# FuelGauge.net
KiCad netlist of a schematic drawn in Altium Designer
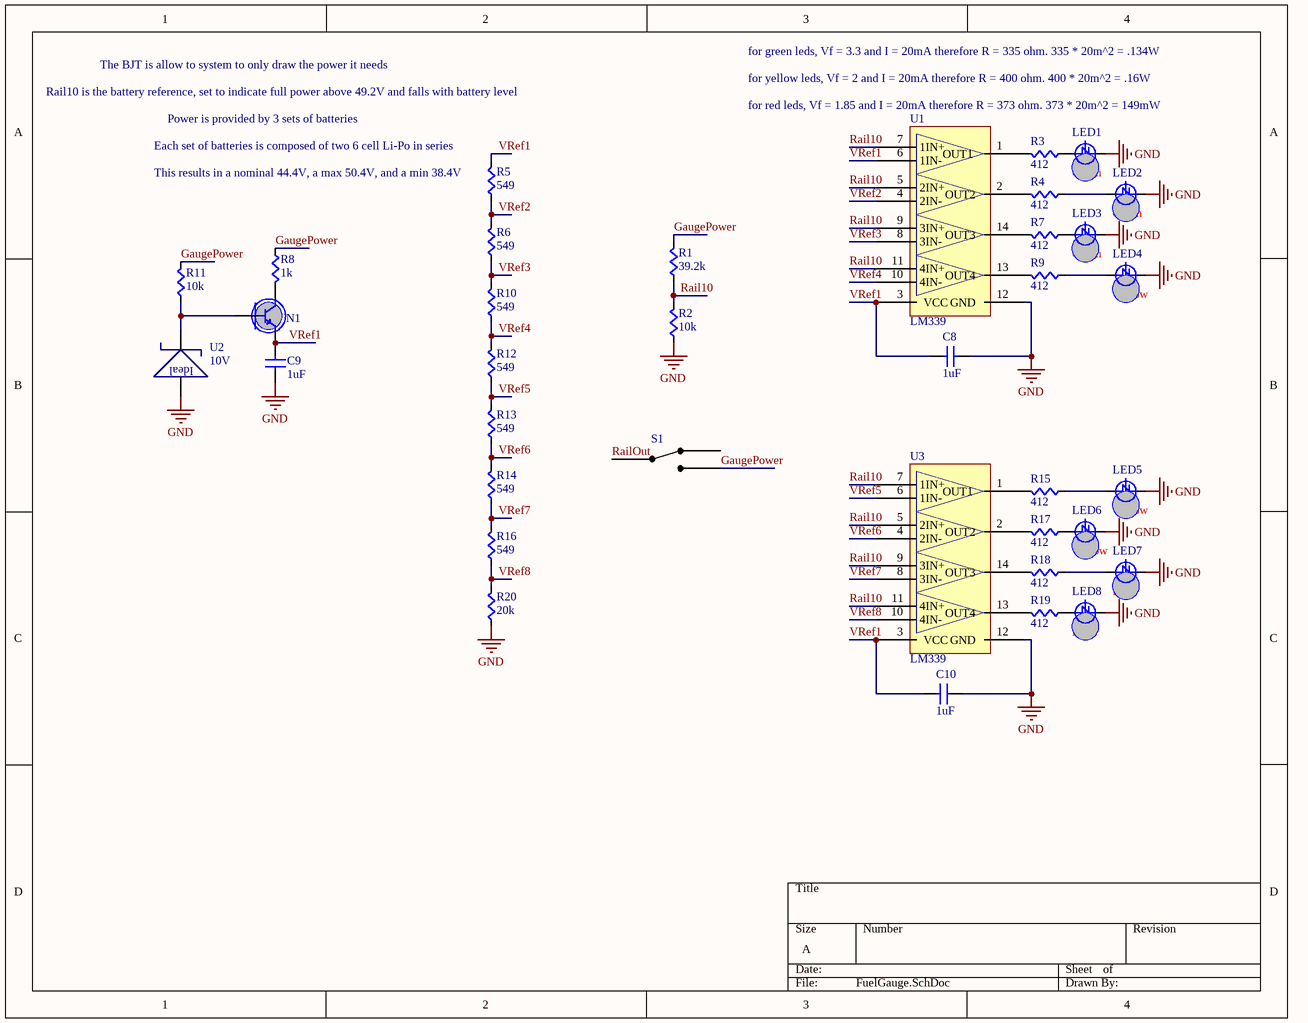
[diagram p0: FuelGauge.SchDoc]

(export (version "E")
  (design (tool "Eeschema 10.0.6"))
  (components
    (comp (ref "C8")
      (value "1uF")
      (footprint "CAPC0603")
      (fields (field (name "Comment") "Cap"))
      (libsource (lib "SubjuGator8") (part "Cap"))
    )
    (comp (ref "C9")
      (value "1uF")
      (footprint "CAPC0603")
      (fields (field (name "Comment") "Cap"))
      (libsource (lib "SubjuGator8") (part "Cap"))
    )
    (comp (ref "C10")
      (value "1uF")
      (footprint "CAPC0603")
      (fields (field (name "Comment") "Cap"))
      (libsource (lib "SubjuGator8") (part "Cap"))
    )
    (comp (ref "LED1")
      (value "LED")
      (footprint "LED0603")
      (fields (field (name "COLOR") "Green"))
      (libsource (lib "SubjuGator8") (part "LED"))
    )
    (comp (ref "LED2")
      (value "LED")
      (footprint "LED0603")
      (fields (field (name "COLOR") "Green"))
      (libsource (lib "SubjuGator8") (part "LED"))
    )
    (comp (ref "LED3")
      (value "LED")
      (footprint "LED0603")
      (fields (field (name "COLOR") "Green"))
      (libsource (lib "SubjuGator8") (part "LED"))
    )
    (comp (ref "LED4")
      (value "LED")
      (footprint "LED0603")
      (fields (field (name "COLOR") "Yellow"))
      (libsource (lib "SubjuGator8") (part "LED"))
    )
    (comp (ref "LED5")
      (value "LED")
      (footprint "LED0603")
      (fields (field (name "COLOR") "Yellow"))
      (libsource (lib "SubjuGator8") (part "LED"))
    )
    (comp (ref "LED6")
      (value "LED")
      (footprint "LED0603")
      (fields (field (name "COLOR") "Yellow"))
      (libsource (lib "SubjuGator8") (part "LED"))
    )
    (comp (ref "LED7")
      (value "LED")
      (footprint "LED0603")
      (fields (field (name "COLOR") "Red"))
      (libsource (lib "SubjuGator8") (part "LED"))
    )
    (comp (ref "LED8")
      (value "LED")
      (footprint "LED0603")
      (fields (field (name "COLOR") "Red"))
      (libsource (lib "SubjuGator8") (part "LED"))
    )
    (comp (ref "N1")
      (value "NPNBJT")
      (footprint "PZT3904")
      (description "NPN Transistor Template")
      (libsource (lib "SubjuGator8") (part "NPNBJT"))
    )
    (comp (ref "R1")
      (value "39.2k")
      (footprint "RES0603")
      (fields (field (name "Comment") "Res"))
      (libsource (lib "SubjuGator8") (part "Res"))
    )
    (comp (ref "R2")
      (value "10k")
      (footprint "RES0603")
      (fields (field (name "Comment") "Res"))
      (libsource (lib "SubjuGator8") (part "Res"))
    )
    (comp (ref "R3")
      (value "412")
      (footprint "RES1206")
      (fields (field (name "Comment") "Res"))
      (libsource (lib "SubjuGator8") (part "Res"))
    )
    (comp (ref "R4")
      (value "412")
      (footprint "RES1206")
      (fields (field (name "Comment") "Res"))
      (libsource (lib "SubjuGator8") (part "Res"))
    )
    (comp (ref "R5")
      (value "549")
      (footprint "RES0603")
      (fields (field (name "Comment") "Res"))
      (libsource (lib "SubjuGator8") (part "Res"))
    )
    (comp (ref "R6")
      (value "549")
      (footprint "RES0603")
      (fields (field (name "Comment") "Res"))
      (libsource (lib "SubjuGator8") (part "Res"))
    )
    (comp (ref "R7")
      (value "412")
      (footprint "RES1206")
      (fields (field (name "Comment") "Res"))
      (libsource (lib "SubjuGator8") (part "Res"))
    )
    (comp (ref "R8")
      (value "1k")
      (footprint "RES1206")
      (fields (field (name "Comment") "Res"))
      (libsource (lib "SubjuGator8") (part "Res"))
    )
    (comp (ref "R9")
      (value "412")
      (footprint "RES1206")
      (fields (field (name "Comment") "Res"))
      (libsource (lib "SubjuGator8") (part "Res"))
    )
    (comp (ref "R10")
      (value "549")
      (footprint "RES0603")
      (fields (field (name "Comment") "Res"))
      (libsource (lib "SubjuGator8") (part "Res"))
    )
    (comp (ref "R11")
      (value "10k")
      (footprint "RES0603")
      (fields (field (name "Comment") "Res"))
      (libsource (lib "SubjuGator8") (part "Res"))
    )
    (comp (ref "R12")
      (value "549")
      (footprint "RES0603")
      (fields (field (name "Comment") "Res"))
      (libsource (lib "SubjuGator8") (part "Res"))
    )
    (comp (ref "R13")
      (value "549")
      (footprint "RES0603")
      (fields (field (name "Comment") "Res"))
      (libsource (lib "SubjuGator8") (part "Res"))
    )
    (comp (ref "R14")
      (value "549")
      (footprint "RES0603")
      (fields (field (name "Comment") "Res"))
      (libsource (lib "SubjuGator8") (part "Res"))
    )
    (comp (ref "R15")
      (value "412")
      (footprint "RES1206")
      (fields (field (name "Comment") "Res"))
      (libsource (lib "SubjuGator8") (part "Res"))
    )
    (comp (ref "R16")
      (value "549")
      (footprint "RES0603")
      (fields (field (name "Comment") "Res"))
      (libsource (lib "SubjuGator8") (part "Res"))
    )
    (comp (ref "R17")
      (value "412")
      (footprint "RES1206")
      (fields (field (name "Comment") "Res"))
      (libsource (lib "SubjuGator8") (part "Res"))
    )
    (comp (ref "R18")
      (value "412")
      (footprint "RES1206")
      (fields (field (name "Comment") "Res"))
      (libsource (lib "SubjuGator8") (part "Res"))
    )
    (comp (ref "R19")
      (value "412")
      (footprint "RES1206")
      (fields (field (name "Comment") "Res"))
      (libsource (lib "SubjuGator8") (part "Res"))
    )
    (comp (ref "R20")
      (value "20k")
      (footprint "RES0603")
      (fields (field (name "Comment") "Res"))
      (libsource (lib "SubjuGator8") (part "Res"))
    )
    (comp (ref "S1")
      (value "SPDT Slide Switch")
      (footprint "CL-SB-12B-01T")
      (libsource (lib "SubjuGator8") (part "SPDT Slide Switch"))
    )
    (comp (ref "U1")
      (value "LM339")
      (footprint "LM339")
      (description "IC QUAD DIFF COMPARATOR 14-TSSOP")
      (libsource (lib "SubjuGator8") (part "LM339"))
    )
    (comp (ref "U2")
      (value "LM4040")
      (footprint "LM4040")
      (description "LM4040AIM3-10.0/NOPBCT")
      (fields (field (name "REVERSE BREAKDOWN VOLTAGE") "10V"))
      (libsource (lib "SubjuGator8") (part "LM4040"))
    )
    (comp (ref "U3")
      (value "LM339")
      (footprint "LM339")
      (description "IC QUAD DIFF COMPARATOR 14-TSSOP")
      (libsource (lib "SubjuGator8") (part "LM339"))
    )
  )
  (nets
    (net (code "1") (name "/GaugePower") (class "Default")
      (node (ref "R1") (pin "1") (pinfunction "A_1") (pintype "passive"))
      (node (ref "R11") (pin "1") (pinfunction "A_1") (pintype "passive"))
      (node (ref "R8") (pin "2") (pinfunction "B_2") (pintype "passive"))
      (node (ref "S1") (pin "3") (pinfunction "3_3") (pintype "passive"))
    )
    (net (code "2") (name "/Rail10") (class "Default")
      (node (ref "R1") (pin "2") (pinfunction "B_2") (pintype "passive"))
      (node (ref "R2") (pin "1") (pinfunction "A_1") (pintype "passive"))
      (node (ref "U1") (pin "11") (pinfunction "4IN+_11") (pintype "passive"))
      (node (ref "U1") (pin "5") (pinfunction "2IN+_5") (pintype "passive"))
      (node (ref "U1") (pin "7") (pinfunction "1IN+_7") (pintype "passive"))
      (node (ref "U1") (pin "9") (pinfunction "3IN+_9") (pintype "passive"))
      (node (ref "U3") (pin "11") (pinfunction "4IN+_11") (pintype "passive"))
      (node (ref "U3") (pin "5") (pinfunction "2IN+_5") (pintype "passive"))
      (node (ref "U3") (pin "7") (pinfunction "1IN+_7") (pintype "passive"))
      (node (ref "U3") (pin "9") (pinfunction "3IN+_9") (pintype "passive"))
    )
    (net (code "3") (name "/RailOut") (class "Default")
      (node (ref "S1") (pin "2") (pinfunction "2_2") (pintype "passive"))
    )
    (net (code "4") (name "/VRef1") (class "Default")
      (node (ref "C10") (pin "1") (pinfunction "A_1") (pintype "passive"))
      (node (ref "C8") (pin "1") (pinfunction "A_1") (pintype "passive"))
      (node (ref "C9") (pin "1") (pinfunction "A_1") (pintype "passive"))
      (node (ref "N1") (pin "E") (pinfunction "E_E") (pintype "passive"))
      (node (ref "R5") (pin "1") (pinfunction "A_1") (pintype "passive"))
      (node (ref "U1") (pin "3") (pinfunction "VCC_3") (pintype "passive"))
      (node (ref "U1") (pin "6") (pinfunction "1IN-_6") (pintype "passive"))
      (node (ref "U3") (pin "3") (pinfunction "VCC_3") (pintype "passive"))
    )
    (net (code "5") (name "/VRef2") (class "Default")
      (node (ref "R5") (pin "2") (pinfunction "B_2") (pintype "passive"))
      (node (ref "R6") (pin "1") (pinfunction "A_1") (pintype "passive"))
      (node (ref "U1") (pin "4") (pinfunction "2IN-_4") (pintype "passive"))
    )
    (net (code "6") (name "/VRef3") (class "Default")
      (node (ref "R10") (pin "1") (pinfunction "A_1") (pintype "passive"))
      (node (ref "R6") (pin "2") (pinfunction "B_2") (pintype "passive"))
      (node (ref "U1") (pin "8") (pinfunction "3IN-_8") (pintype "passive"))
    )
    (net (code "7") (name "/VRef4") (class "Default")
      (node (ref "R10") (pin "2") (pinfunction "B_2") (pintype "passive"))
      (node (ref "R12") (pin "1") (pinfunction "A_1") (pintype "passive"))
      (node (ref "U1") (pin "10") (pinfunction "4IN-_10") (pintype "passive"))
    )
    (net (code "8") (name "/VRef5") (class "Default")
      (node (ref "R12") (pin "2") (pinfunction "B_2") (pintype "passive"))
      (node (ref "R13") (pin "1") (pinfunction "A_1") (pintype "passive"))
      (node (ref "U3") (pin "6") (pinfunction "1IN-_6") (pintype "passive"))
    )
    (net (code "9") (name "/VRef6") (class "Default")
      (node (ref "R13") (pin "2") (pinfunction "B_2") (pintype "passive"))
      (node (ref "R14") (pin "1") (pinfunction "A_1") (pintype "passive"))
      (node (ref "U3") (pin "4") (pinfunction "2IN-_4") (pintype "passive"))
    )
    (net (code "10") (name "/VRef7") (class "Default")
      (node (ref "R14") (pin "2") (pinfunction "B_2") (pintype "passive"))
      (node (ref "R16") (pin "1") (pinfunction "A_1") (pintype "passive"))
      (node (ref "U3") (pin "8") (pinfunction "3IN-_8") (pintype "passive"))
    )
    (net (code "11") (name "/VRef8") (class "Default")
      (node (ref "R16") (pin "2") (pinfunction "B_2") (pintype "passive"))
      (node (ref "R20") (pin "1") (pinfunction "A_1") (pintype "passive"))
      (node (ref "U3") (pin "10") (pinfunction "4IN-_10") (pintype "passive"))
    )
    (net (code "12") (name "GND") (class "Default")
      (node (ref "C10") (pin "2") (pinfunction "B_2") (pintype "passive"))
      (node (ref "C8") (pin "2") (pinfunction "B_2") (pintype "passive"))
      (node (ref "C9") (pin "2") (pinfunction "B_2") (pintype "passive"))
      (node (ref "LED1") (pin "C") (pinfunction "C_C") (pintype "passive"))
      (node (ref "LED2") (pin "C") (pinfunction "C_C") (pintype "passive"))
      (node (ref "LED3") (pin "C") (pinfunction "C_C") (pintype "passive"))
      (node (ref "LED4") (pin "C") (pinfunction "C_C") (pintype "passive"))
      (node (ref "LED5") (pin "C") (pinfunction "C_C") (pintype "passive"))
      (node (ref "LED6") (pin "C") (pinfunction "C_C") (pintype "passive"))
      (node (ref "LED7") (pin "C") (pinfunction "C_C") (pintype "passive"))
      (node (ref "LED8") (pin "C") (pinfunction "C_C") (pintype "passive"))
      (node (ref "R2") (pin "2") (pinfunction "B_2") (pintype "passive"))
      (node (ref "R20") (pin "2") (pinfunction "B_2") (pintype "passive"))
      (node (ref "U1") (pin "12") (pinfunction "GND_12") (pintype "passive"))
      (node (ref "U2") (pin "2") (pinfunction "Cathode_2") (pintype "passive"))
      (node (ref "U3") (pin "12") (pinfunction "GND_12") (pintype "passive"))
    )
    (net (code "13") (name "Net-(R3-A)") (class "Default")
      (node (ref "R3") (pin "1") (pinfunction "A_1") (pintype "passive"))
      (node (ref "U1") (pin "1") (pinfunction "OUT1_1") (pintype "passive"))
    )
    (net (code "14") (name "Net-(R3-B)") (class "Default")
      (node (ref "LED1") (pin "A") (pinfunction "A_A") (pintype "passive"))
      (node (ref "R3") (pin "2") (pinfunction "B_2") (pintype "passive"))
    )
    (net (code "15") (name "Net-(R4-A)") (class "Default")
      (node (ref "R4") (pin "1") (pinfunction "A_1") (pintype "passive"))
      (node (ref "U1") (pin "2") (pinfunction "OUT2_2") (pintype "passive"))
    )
    (net (code "16") (name "Net-(R4-B)") (class "Default")
      (node (ref "LED2") (pin "A") (pinfunction "A_A") (pintype "passive"))
      (node (ref "R4") (pin "2") (pinfunction "B_2") (pintype "passive"))
    )
    (net (code "17") (name "Net-(R7-A)") (class "Default")
      (node (ref "R7") (pin "1") (pinfunction "A_1") (pintype "passive"))
      (node (ref "U1") (pin "14") (pinfunction "OUT3_14") (pintype "passive"))
    )
    (net (code "18") (name "Net-(R7-B)") (class "Default")
      (node (ref "LED3") (pin "A") (pinfunction "A_A") (pintype "passive"))
      (node (ref "R7") (pin "2") (pinfunction "B_2") (pintype "passive"))
    )
    (net (code "19") (name "Net-(R8-A)") (class "Default")
      (node (ref "N1") (pin "C") (pinfunction "C_C") (pintype "passive"))
      (node (ref "R8") (pin "1") (pinfunction "A_1") (pintype "passive"))
    )
    (net (code "20") (name "Net-(R9-A)") (class "Default")
      (node (ref "R9") (pin "1") (pinfunction "A_1") (pintype "passive"))
      (node (ref "U1") (pin "13") (pinfunction "OUT4_13") (pintype "passive"))
    )
    (net (code "21") (name "Net-(R9-B)") (class "Default")
      (node (ref "LED4") (pin "A") (pinfunction "A_A") (pintype "passive"))
      (node (ref "R9") (pin "2") (pinfunction "B_2") (pintype "passive"))
    )
    (net (code "22") (name "Net-(R11-B)") (class "Default")
      (node (ref "N1") (pin "B") (pinfunction "B_B") (pintype "passive"))
      (node (ref "R11") (pin "2") (pinfunction "B_2") (pintype "passive"))
      (node (ref "U2") (pin "1") (pinfunction "Anode_1") (pintype "passive"))
    )
    (net (code "23") (name "Net-(R15-A)") (class "Default")
      (node (ref "R15") (pin "1") (pinfunction "A_1") (pintype "passive"))
      (node (ref "U3") (pin "1") (pinfunction "OUT1_1") (pintype "passive"))
    )
    (net (code "24") (name "Net-(R15-B)") (class "Default")
      (node (ref "LED5") (pin "A") (pinfunction "A_A") (pintype "passive"))
      (node (ref "R15") (pin "2") (pinfunction "B_2") (pintype "passive"))
    )
    (net (code "25") (name "Net-(R17-A)") (class "Default")
      (node (ref "R17") (pin "1") (pinfunction "A_1") (pintype "passive"))
      (node (ref "U3") (pin "2") (pinfunction "OUT2_2") (pintype "passive"))
    )
    (net (code "26") (name "Net-(R17-B)") (class "Default")
      (node (ref "LED6") (pin "A") (pinfunction "A_A") (pintype "passive"))
      (node (ref "R17") (pin "2") (pinfunction "B_2") (pintype "passive"))
    )
    (net (code "27") (name "Net-(R18-A)") (class "Default")
      (node (ref "R18") (pin "1") (pinfunction "A_1") (pintype "passive"))
      (node (ref "U3") (pin "14") (pinfunction "OUT3_14") (pintype "passive"))
    )
    (net (code "28") (name "Net-(R18-B)") (class "Default")
      (node (ref "LED7") (pin "A") (pinfunction "A_A") (pintype "passive"))
      (node (ref "R18") (pin "2") (pinfunction "B_2") (pintype "passive"))
    )
    (net (code "29") (name "Net-(R19-A)") (class "Default")
      (node (ref "R19") (pin "1") (pinfunction "A_1") (pintype "passive"))
      (node (ref "U3") (pin "13") (pinfunction "OUT4_13") (pintype "passive"))
    )
    (net (code "30") (name "Net-(R19-B)") (class "Default")
      (node (ref "LED8") (pin "A") (pinfunction "A_A") (pintype "passive"))
      (node (ref "R19") (pin "2") (pinfunction "B_2") (pintype "passive"))
    )
    (net (code "31") (name "unconnected-(S1-Pad1)") (class "Default")
      (node (ref "S1") (pin "1") (pinfunction "1_1") (pintype "passive"))
    )
  )
)
